# reg_breadboard.net
KiCad netlist of a schematic drawn in EAGLE
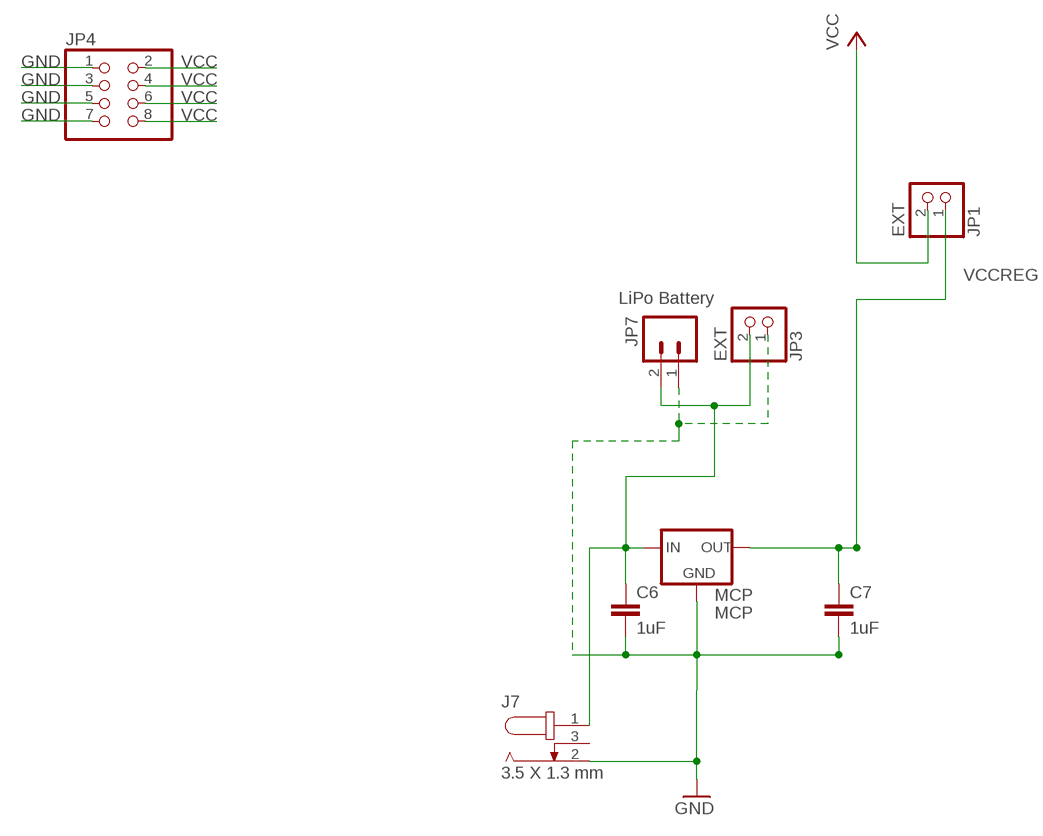
[diagram p0: schematic, sheet 1]

(export (version "E")
  (design (tool "Eeschema 10.0.6"))
  (components
    (comp (ref "C6")
      (value "1uF")
      (footprint "eagle-import:C0805")
      (libsource (lib "eagle-import") (part "C-EUC0805"))
    )
    (comp (ref "C7")
      (value "1uF")
      (footprint "eagle-import:C0805")
      (libsource (lib "eagle-import") (part "C-EUC0805"))
    )
    (comp (ref "J7")
      (value "3.5 X 1.3 mm")
      (footprint "eagle-import:3.5X1.3MM_DC_JACK")
      (libsource (lib "eagle-import") (part "DC_JACK_3.5X1.3MM"))
    )
    (comp (ref "JP1")
      (value "EXT")
      (footprint "eagle-import:1X02")
      (libsource (lib "eagle-import") (part "PINHD-1X2"))
    )
    (comp (ref "JP3")
      (value "EXT")
      (footprint "eagle-import:1X02")
      (libsource (lib "eagle-import") (part "PINHD-1X2"))
    )
    (comp (ref "JP4")
      (value "PINHD-2X4")
      (footprint "eagle-import:2X04")
      (libsource (lib "eagle-import") (part "PINHD-2X4"))
    )
    (comp (ref "JP7")
      (value "LiPo Battery")
      (footprint "eagle-import:JST-2-PTH")
      (libsource (lib "eagle-import") (part "M02JST-PTH-2"))
    )
    (comp (ref "MCP")
      (value "MCP")
      (footprint "eagle-import:SOT-23")
      (libsource (lib "eagle-import") (part "MCP1700SOT-23"))
    )
  )
  (nets
    (net (code "1") (name "GND") (class "Default")
      (node (ref "C6") (pin "2") (pinfunction "2_2") (pintype "passive"))
      (node (ref "C7") (pin "2") (pinfunction "2_2") (pintype "passive"))
      (node (ref "J7") (pin "2") (pinfunction "2_2") (pintype "passive"))
      (node (ref "JP3") (pin "1") (pinfunction "1_1") (pintype "passive"))
      (node (ref "JP4") (pin "1") (pinfunction "1_1") (pintype "passive"))
      (node (ref "JP4") (pin "3") (pinfunction "3_3") (pintype "passive"))
      (node (ref "JP4") (pin "5") (pinfunction "5_5") (pintype "passive"))
      (node (ref "JP4") (pin "7") (pinfunction "7_7") (pintype "passive"))
      (node (ref "JP7") (pin "1") (pinfunction "1_1") (pintype "passive"))
      (node (ref "MCP") (pin "1") (pinfunction "GND_1") (pintype "input"))
    )
    (net (code "2") (name "Net-(MCP-IN)") (class "Default")
      (node (ref "C6") (pin "1") (pinfunction "1_1") (pintype "passive"))
      (node (ref "J7") (pin "1") (pinfunction "1_1") (pintype "passive"))
      (node (ref "JP3") (pin "2") (pinfunction "2_2") (pintype "passive"))
      (node (ref "JP7") (pin "2") (pinfunction "2_2") (pintype "passive"))
      (node (ref "MCP") (pin "3") (pinfunction "IN_3") (pintype "input"))
    )
    (net (code "3") (name "VCC") (class "Default")
      (node (ref "JP1") (pin "2") (pinfunction "2_2") (pintype "passive"))
      (node (ref "JP4") (pin "2") (pinfunction "2_2") (pintype "passive"))
      (node (ref "JP4") (pin "4") (pinfunction "4_4") (pintype "passive"))
      (node (ref "JP4") (pin "6") (pinfunction "6_6") (pintype "passive"))
      (node (ref "JP4") (pin "8") (pinfunction "8_8") (pintype "passive"))
    )
    (net (code "4") (name "VCCREG") (class "Default")
      (node (ref "C7") (pin "1") (pinfunction "1_1") (pintype "passive"))
      (node (ref "JP1") (pin "1") (pinfunction "1_1") (pintype "passive"))
      (node (ref "MCP") (pin "2") (pinfunction "OUT_2") (pintype "passive"))
    )
    (net (code "5") (name "unconnected-(J7-Pad3)") (class "Default")
      (node (ref "J7") (pin "3") (pinfunction "3_3") (pintype "passive"))
    )
  )
)
